# SY_HR08_MCU_MOTOR_V1_1.net
KiCad netlist of a schematic drawn in Altium Designer
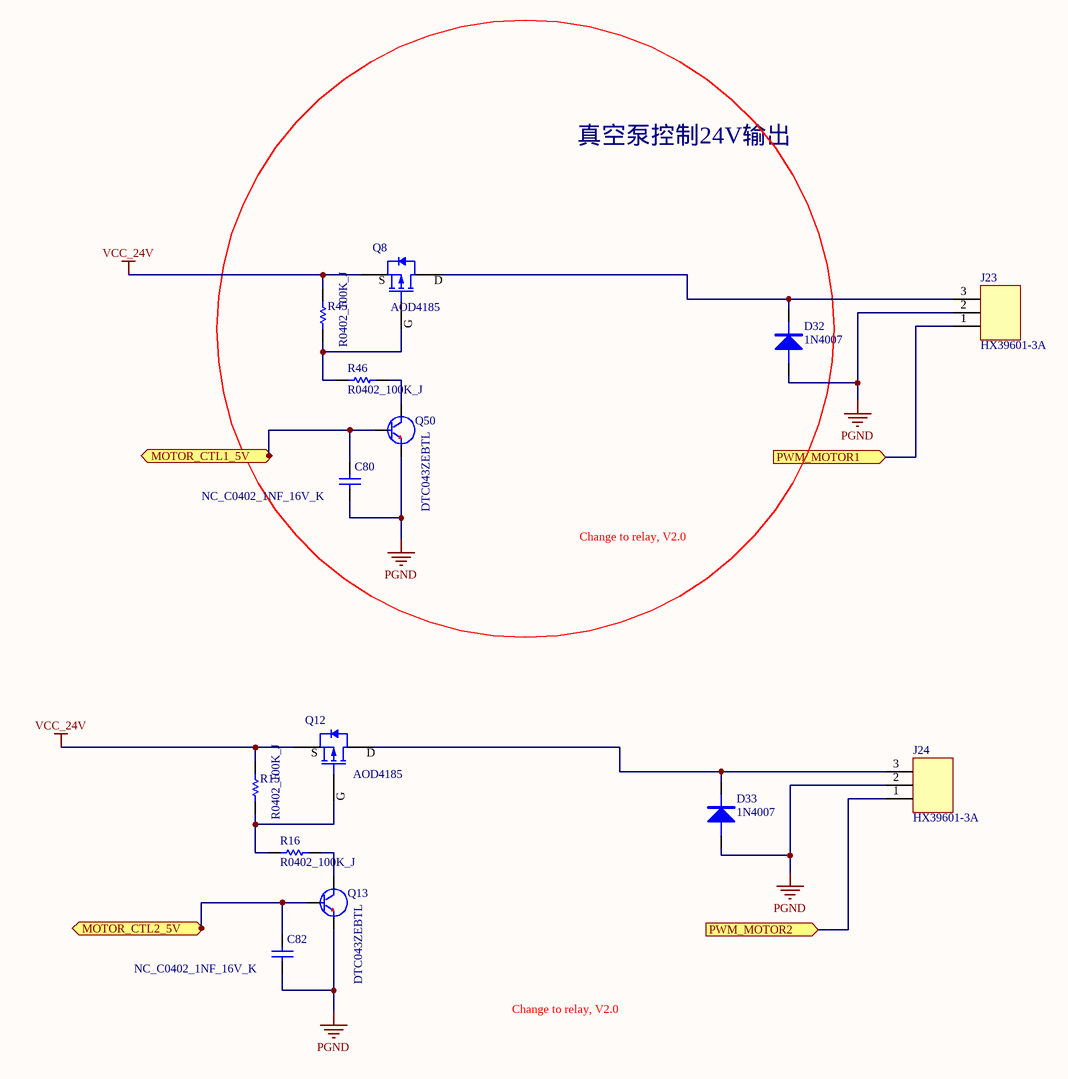
[diagram p0: SY_HR08_MCU_MOTOR_V1.1.SchDoc]

(export (version "E")
  (design (tool "Eeschema 10.0.6"))
  (components
    (comp (ref "C80")
      (value "NC_C0402_1NF_16V_K")
      (footprint "CAP0402_HQ")
      (description "电容_100nF_0402_X7R_16V_K")
      (libsource (lib "zhangky_sch") (part "C0402_100NF_16V_K"))
    )
    (comp (ref "C82")
      (value "NC_C0402_1NF_16V_K")
      (footprint "CAP0402_HQ")
      (description "电容_100nF_0402_X7R_16V_K")
      (libsource (lib "zhangky_sch") (part "C0402_100NF_16V_K"))
    )
    (comp (ref "D32")
      (value "1N4007")
      (footprint "1N4007")
      (description "1N4007 整流二极管 1A 1000V")
      (libsource (lib "zhangky_sch") (part "1N4007"))
    )
    (comp (ref "D33")
      (value "1N4007")
      (footprint "1N4007")
      (description "1N4007 整流二极管 1A 1000V")
      (libsource (lib "zhangky_sch") (part "1N4007"))
    )
    (comp (ref "J23")
      (value "HX39601-3A")
      (footprint "HX39601-3A")
      (description "HX39601-3A 3.96mm")
      (libsource (lib "zhangky_sch") (part "HX39601-3A"))
    )
    (comp (ref "J24")
      (value "HX39601-3A")
      (footprint "HX39601-3A")
      (description "HX39601-3A 3.96mm")
      (libsource (lib "zhangky_sch") (part "HX39601-3A"))
    )
    (comp (ref "Q8")
      (value "AOD4185")
      (footprint "TO-252")
      (description "PMOS  TO252")
      (libsource (lib "zhangky_sch") (part "PMOS  TO252"))
    )
    (comp (ref "Q12")
      (value "AOD4185")
      (footprint "TO-252")
      (description "PMOS  TO252")
      (libsource (lib "zhangky_sch") (part "PMOS  TO252"))
    )
    (comp (ref "Q13")
      (value "DTC043ZEBTL")
      (footprint "DTC043ZEBTL$2F$$2F$DTC143ZE$2F$$2F$LDTC143ZET1G")
      (description "NPN三极管_100mA_EMT3F")
      (libsource (lib "zhangky_sch") (part "DTC043ZEBTL"))
    )
    (comp (ref "Q50")
      (value "DTC043ZEBTL")
      (footprint "DTC043ZEBTL$2F$$2F$DTC143ZE$2F$$2F$LDTC143ZET1G")
      (description "NPN三极管_100mA_EMT3F")
      (libsource (lib "zhangky_sch") (part "DTC043ZEBTL"))
    )
    (comp (ref "R15")
      (value "R0402_100K_J")
      (footprint "RES0402_HQ")
      (description "电阻100K(0402-0.0625W-J)")
      (libsource (lib "zhangky_sch") (part "R0402_100K_J"))
    )
    (comp (ref "R16")
      (value "R0402_100K_J")
      (footprint "RES0402_HQ")
      (description "电阻100K(0402-0.0625W-J)")
      (libsource (lib "zhangky_sch") (part "R0402_100K_J"))
    )
    (comp (ref "R45")
      (value "R0402_100K_J")
      (footprint "RES0402_HQ")
      (description "电阻100K(0402-0.0625W-J)")
      (libsource (lib "zhangky_sch") (part "R0402_100K_J"))
    )
    (comp (ref "R46")
      (value "R0402_100K_J")
      (footprint "RES0402_HQ")
      (description "电阻100K(0402-0.0625W-J)")
      (libsource (lib "zhangky_sch") (part "R0402_100K_J"))
    )
  )
  (nets
    (net (code "3") (name "/PWM_MOTOR1") (class "Default")
      (node (ref "J23") (pin "1") (pinfunction "1_1") (pintype "passive"))
    )
    (net (code "4") (name "/PWM_MOTOR2") (class "Default")
      (node (ref "J24") (pin "1") (pinfunction "1_1") (pintype "passive"))
    )
    (net (code "5") (name "Net-(Q8-D)") (class "Default")
      (node (ref "D32") (pin "1") (pinfunction "1_1") (pintype "passive"))
      (node (ref "J23") (pin "3") (pinfunction "3_3") (pintype "passive"))
      (node (ref "Q8") (pin "3") (pinfunction "D_3") (pintype "passive"))
    )
    (net (code "6") (name "Net-(Q8-G)") (class "Default")
      (node (ref "Q8") (pin "1") (pinfunction "G_1") (pintype "passive"))
      (node (ref "R45") (pin "1") (pinfunction "1_1") (pintype "passive"))
      (node (ref "R46") (pin "2") (pinfunction "2_2") (pintype "passive"))
    )
    (net (code "7") (name "Net-(Q12-D)") (class "Default")
      (node (ref "D33") (pin "1") (pinfunction "1_1") (pintype "passive"))
      (node (ref "J24") (pin "3") (pinfunction "3_3") (pintype "passive"))
      (node (ref "Q12") (pin "3") (pinfunction "D_3") (pintype "passive"))
    )
    (net (code "8") (name "Net-(Q12-G)") (class "Default")
      (node (ref "Q12") (pin "1") (pinfunction "G_1") (pintype "passive"))
      (node (ref "R15") (pin "1") (pinfunction "1_1") (pintype "passive"))
      (node (ref "R16") (pin "2") (pinfunction "2_2") (pintype "passive"))
    )
    (net (code "9") (name "Net-(Q13-B)") (class "Default")
      (node (ref "C82") (pin "1") (pinfunction "1_1") (pintype "passive"))
      (node (ref "Q13") (pin "1") (pinfunction "B_1") (pintype "passive"))
    )
    (net (code "10") (name "Net-(Q13-C)") (class "Default")
      (node (ref "Q13") (pin "3") (pinfunction "C_3") (pintype "passive"))
      (node (ref "R16") (pin "1") (pinfunction "1_1") (pintype "passive"))
    )
    (net (code "11") (name "Net-(Q50-B)") (class "Default")
      (node (ref "C80") (pin "1") (pinfunction "1_1") (pintype "passive"))
      (node (ref "Q50") (pin "1") (pinfunction "B_1") (pintype "passive"))
    )
    (net (code "12") (name "Net-(Q50-C)") (class "Default")
      (node (ref "Q50") (pin "3") (pinfunction "C_3") (pintype "passive"))
      (node (ref "R46") (pin "1") (pinfunction "1_1") (pintype "passive"))
    )
    (net (code "13") (name "PGND") (class "Default")
      (node (ref "C80") (pin "2") (pinfunction "2_2") (pintype "passive"))
      (node (ref "C82") (pin "2") (pinfunction "2_2") (pintype "passive"))
      (node (ref "D32") (pin "2") (pinfunction "2_2") (pintype "passive"))
      (node (ref "D33") (pin "2") (pinfunction "2_2") (pintype "passive"))
      (node (ref "J23") (pin "2") (pinfunction "2_2") (pintype "passive"))
      (node (ref "J24") (pin "2") (pinfunction "2_2") (pintype "passive"))
      (node (ref "Q13") (pin "2") (pinfunction "E_2") (pintype "passive"))
      (node (ref "Q50") (pin "2") (pinfunction "E_2") (pintype "passive"))
    )
    (net (code "14") (name "VCC_24V") (class "Default")
      (node (ref "Q12") (pin "2") (pinfunction "S_2") (pintype "passive"))
      (node (ref "Q8") (pin "2") (pinfunction "S_2") (pintype "passive"))
      (node (ref "R15") (pin "2") (pinfunction "2_2") (pintype "passive"))
      (node (ref "R45") (pin "2") (pinfunction "2_2") (pintype "passive"))
    )
  )
)
